# portalusbhub.net
KiCad netlist of a schematic drawn in EasyEDA Pro
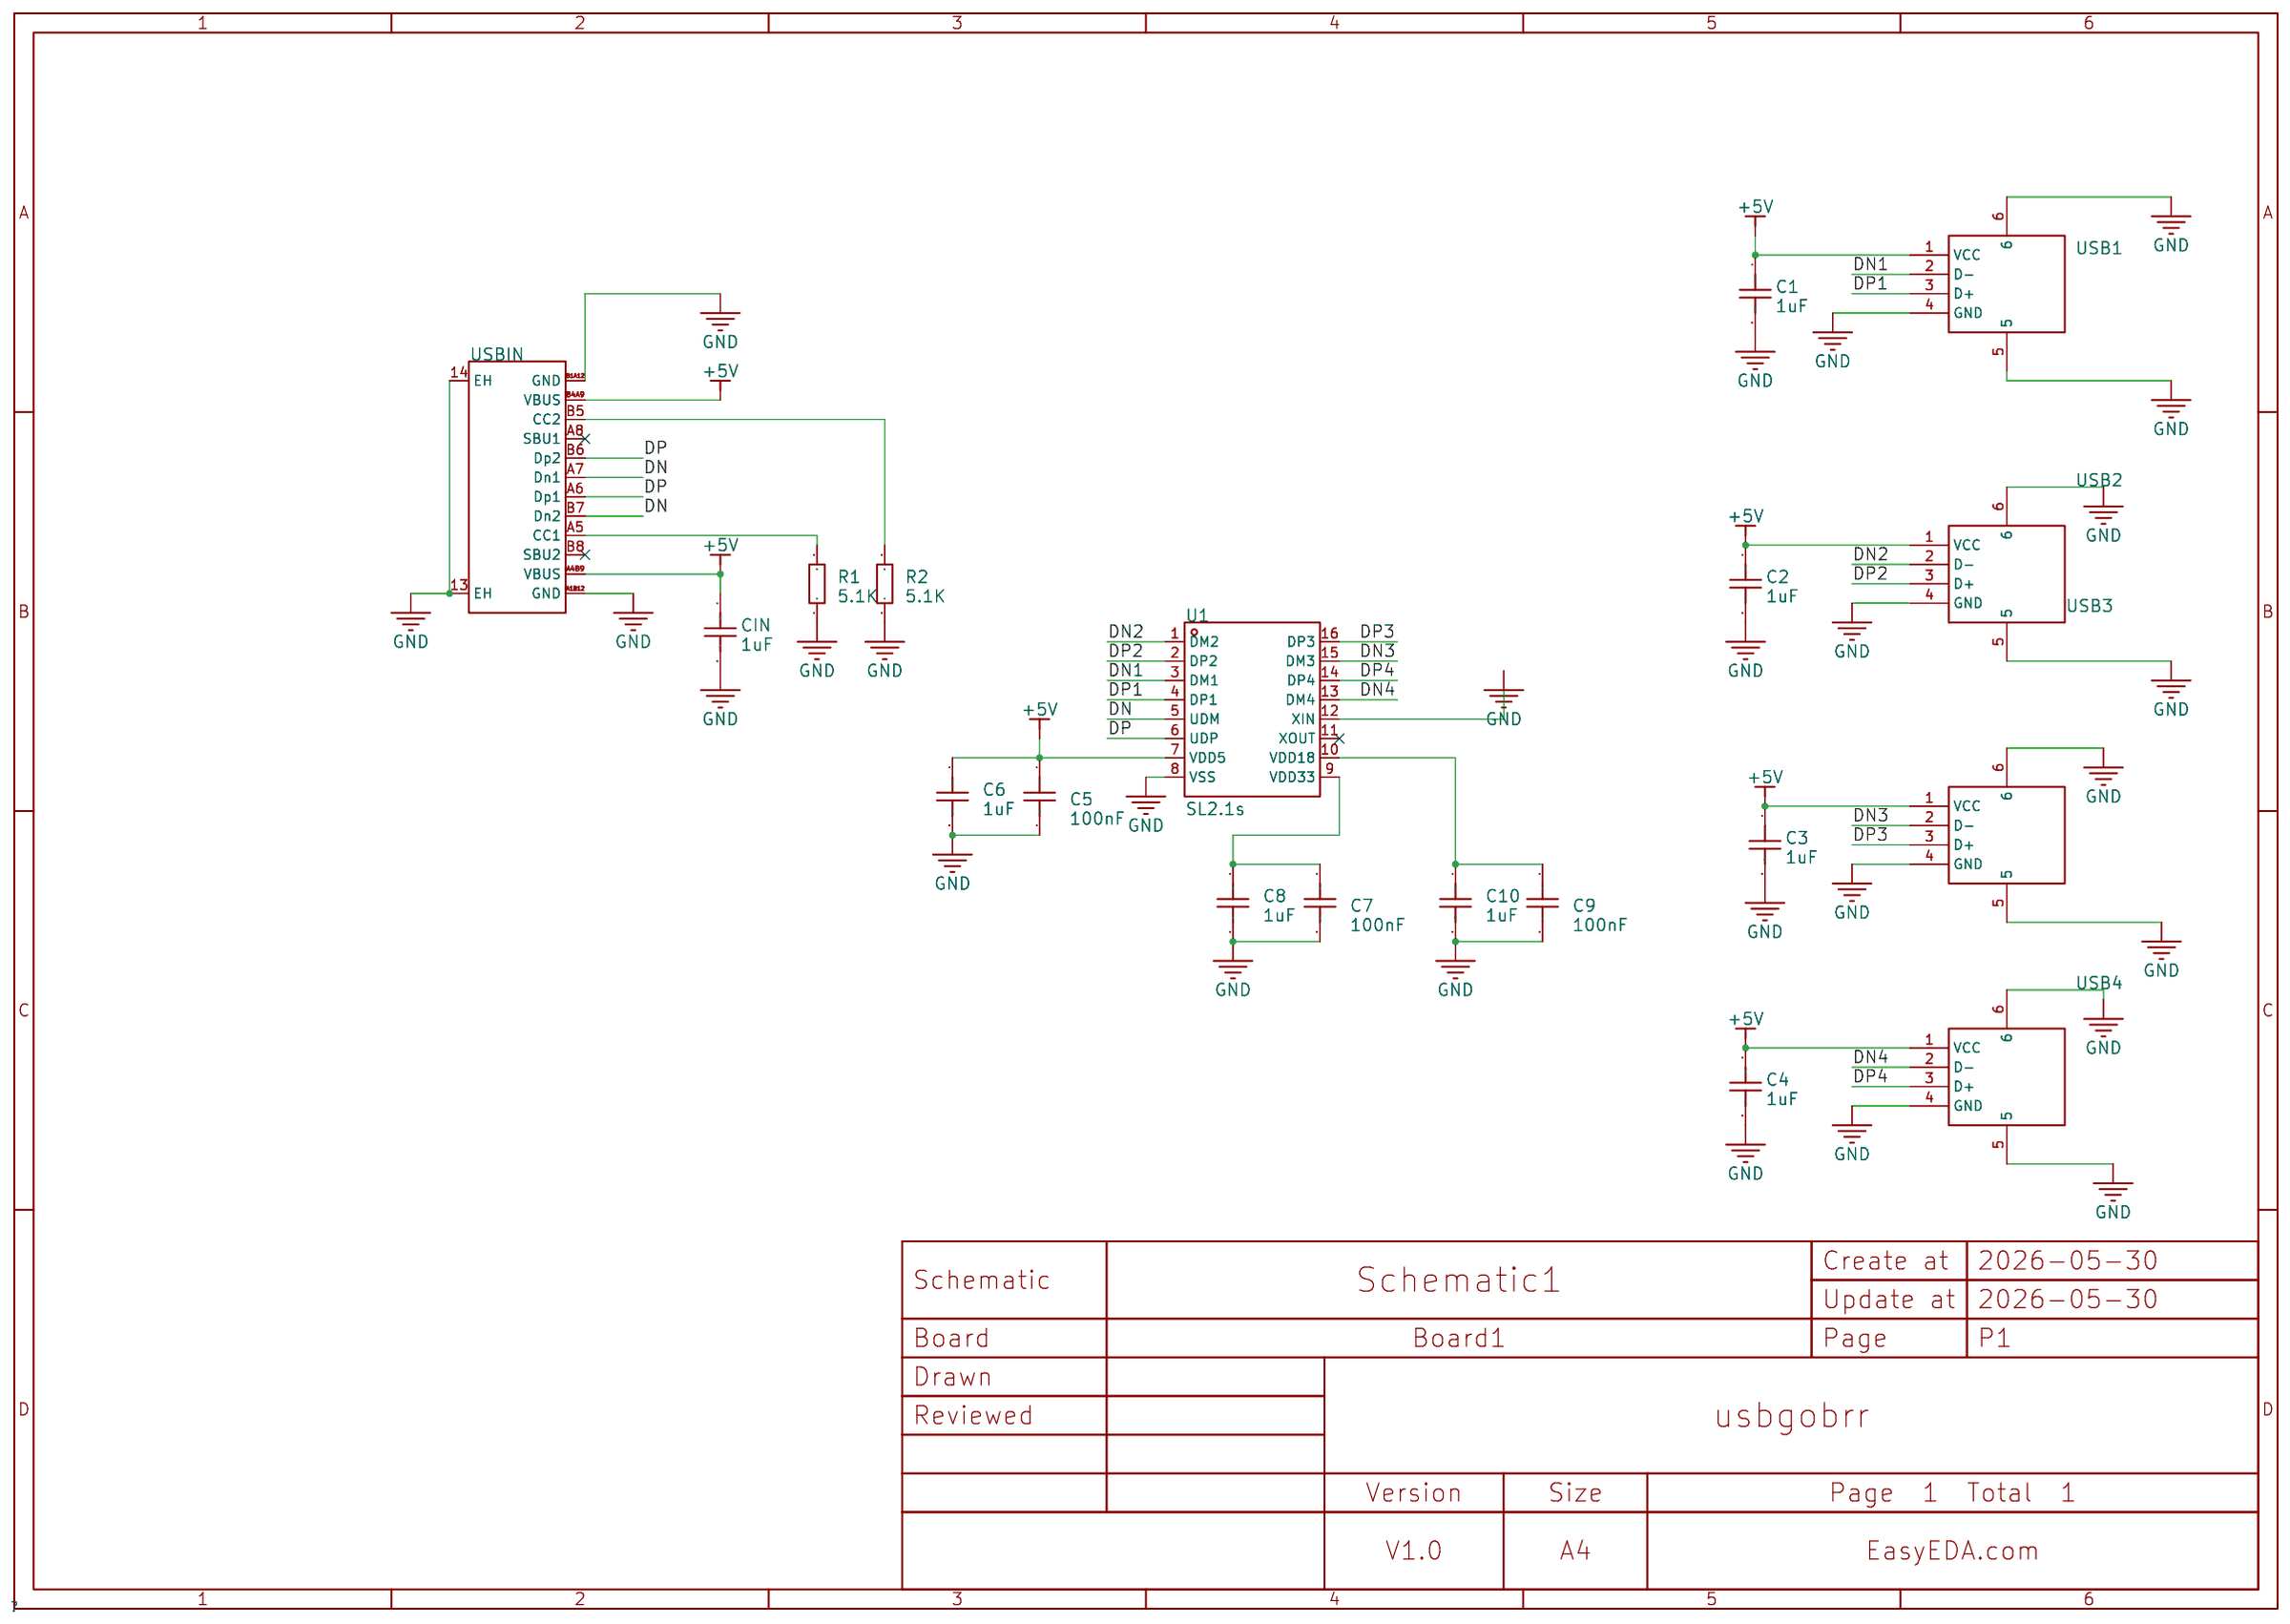
[diagram p0: schematic sheet]

(export (version "E")
  (design (tool "Eeschema 10.0.6"))
  (components
    (comp (ref "C1") (value "1uF") (footprint "easyedapro:C0603") (libsource (lib "easyedapro") (part "CAP")))
    (comp (ref "C2") (value "1uF") (footprint "easyedapro:C0603") (libsource (lib "easyedapro") (part "CAP")))
    (comp (ref "C3") (value "1uF") (footprint "easyedapro:C0603") (libsource (lib "easyedapro") (part "CAP")))
    (comp (ref "C4") (value "1uF") (footprint "easyedapro:C0603") (libsource (lib "easyedapro") (part "CAP")))
    (comp (ref "C5")
      (value "100nF")
      (footprint "easyedapro:C0603")
      (libsource (lib "easyedapro") (part "CAP"))
    )
    (comp (ref "C6") (value "1uF") (footprint "easyedapro:C0603") (libsource (lib "easyedapro") (part "CAP")))
    (comp (ref "C7")
      (value "100nF")
      (footprint "easyedapro:C0603")
      (libsource (lib "easyedapro") (part "CAP"))
    )
    (comp (ref "C8") (value "1uF") (footprint "easyedapro:C0603") (libsource (lib "easyedapro") (part "CAP")))
    (comp (ref "C9")
      (value "100nF")
      (footprint "easyedapro:C0603")
      (libsource (lib "easyedapro") (part "CAP"))
    )
    (comp (ref "C10")
      (value "1uF")
      (footprint "easyedapro:C0603")
      (libsource (lib "easyedapro") (part "CAP"))
    )
    (comp (ref "CIN")
      (value "1uF")
      (footprint "easyedapro:C0603")
      (libsource (lib "easyedapro") (part "CAP"))
    )
    (comp (ref "R1")
      (value "5.1K")
      (footprint "easyedapro:R0603")
      (libsource (lib "easyedapro") (part "Res"))
    )
    (comp (ref "R2")
      (value "5.1K")
      (footprint "easyedapro:R0603")
      (libsource (lib "easyedapro") (part "Res"))
    )
    (comp (ref "U1")
      (value "SL2.1s")
      (footprint "easyedapro:SSOP-16_L4.6-W2.6-P0.53-LS4.0-BL")
      (fields (field (name "Manufacturer") "CoreChips(和芯润德)"))
      (libsource (lib "easyedapro") (part "SL2.1S"))
    )
    (comp (ref "USB1")
      (value "10.0 QHHTZB6.3")
      (footprint "easyedapro:USB-A-TH_10.0QHHTZB6.3")
      (fields (field (name "Manufacturer") "SHOU HAN(首韩)"))
      (libsource (lib "easyedapro") (part "10.0 QHHTZB6.3"))
    )
    (comp (ref "USB2")
      (value "10.0 QHHTZB6.3")
      (footprint "easyedapro:USB-A-TH_10.0QHHTZB6.3")
      (fields (field (name "Manufacturer") "SHOU HAN(首韩)"))
      (libsource (lib "easyedapro") (part "10.0 QHHTZB6.3"))
    )
    (comp (ref "USB3")
      (value "10.0 QHHTZB6.3")
      (footprint "easyedapro:USB-A-TH_10.0QHHTZB6.3")
      (fields (field (name "Manufacturer") "SHOU HAN(首韩)"))
      (libsource (lib "easyedapro") (part "10.0 QHHTZB6.3"))
    )
    (comp (ref "USB4")
      (value "10.0 QHHTZB6.3")
      (footprint "easyedapro:USB-A-TH_10.0QHHTZB6.3")
      (fields (field (name "Manufacturer") "SHOU HAN(首韩)"))
      (libsource (lib "easyedapro") (part "10.0 QHHTZB6.3"))
    )
    (comp (ref "USBIN")
      (value "TYPE-C 16PIN 2MD(073)")
      (footprint "easyedapro:USB-C-SMD_TYPE-C-16PIN-2MD-073")
      (fields (field (name "Manufacturer") "SHOU HAN(首韩)"))
      (libsource (lib "easyedapro") (part "TYPE-C 16PIN 2MD(073)"))
    )
  )
  (nets
    (net (code "1") (name "+5V") (class "Default")
      (node (ref "C1") (pin "1") (pinfunction "1_1") (pintype "input"))
      (node (ref "C2") (pin "1") (pinfunction "1_1") (pintype "input"))
      (node (ref "C3") (pin "1") (pinfunction "1_1") (pintype "input"))
      (node (ref "C4") (pin "1") (pinfunction "1_1") (pintype "input"))
      (node (ref "C5") (pin "1") (pinfunction "1_1") (pintype "input"))
      (node (ref "C6") (pin "1") (pinfunction "1_1") (pintype "input"))
      (node (ref "CIN") (pin "1") (pinfunction "1_1") (pintype "input"))
      (node (ref "U1") (pin "7") (pinfunction "VDD5_7") (pintype "unspecified"))
      (node (ref "USB1") (pin "1") (pinfunction "VCC_1") (pintype "unspecified"))
      (node (ref "USB2") (pin "1") (pinfunction "VCC_1") (pintype "unspecified"))
      (node (ref "USB3") (pin "1") (pinfunction "VCC_1") (pintype "unspecified"))
      (node (ref "USB4") (pin "1") (pinfunction "VCC_1") (pintype "unspecified"))
      (node (ref "USBIN") (pin "A4B9") (pinfunction "VBUS_A4B9") (pintype "unspecified"))
      (node (ref "USBIN") (pin "B4A9") (pinfunction "VBUS_B4A9") (pintype "unspecified"))
    )
    (net (code "2") (name "/DN") (class "Default")
      (node (ref "U1") (pin "5") (pinfunction "UDM_5") (pintype "unspecified"))
      (node (ref "USBIN") (pin "A7") (pinfunction "Dn1_A7") (pintype "unspecified"))
      (node (ref "USBIN") (pin "B7") (pinfunction "Dn2_B7") (pintype "unspecified"))
    )
    (net (code "3") (name "/DN1") (class "Default")
      (node (ref "U1") (pin "3") (pinfunction "DM1_3") (pintype "unspecified"))
      (node (ref "USB1") (pin "2") (pinfunction "D-_2") (pintype "unspecified"))
    )
    (net (code "4") (name "/DN2") (class "Default")
      (node (ref "U1") (pin "1") (pinfunction "DM2_1") (pintype "unspecified"))
      (node (ref "USB2") (pin "2") (pinfunction "D-_2") (pintype "unspecified"))
    )
    (net (code "5") (name "/DN3") (class "Default")
      (node (ref "U1") (pin "15") (pinfunction "DM3_15") (pintype "unspecified"))
      (node (ref "USB3") (pin "2") (pinfunction "D-_2") (pintype "unspecified"))
    )
    (net (code "6") (name "/DN4") (class "Default")
      (node (ref "U1") (pin "13") (pinfunction "DM4_13") (pintype "unspecified"))
      (node (ref "USB4") (pin "2") (pinfunction "D-_2") (pintype "unspecified"))
    )
    (net (code "7") (name "/DP") (class "Default")
      (node (ref "U1") (pin "6") (pinfunction "UDP_6") (pintype "unspecified"))
      (node (ref "USBIN") (pin "A6") (pinfunction "Dp1_A6") (pintype "unspecified"))
      (node (ref "USBIN") (pin "B6") (pinfunction "Dp2_B6") (pintype "unspecified"))
    )
    (net (code "8") (name "/DP1") (class "Default")
      (node (ref "U1") (pin "4") (pinfunction "DP1_4") (pintype "unspecified"))
      (node (ref "USB1") (pin "3") (pinfunction "D+_3") (pintype "unspecified"))
    )
    (net (code "9") (name "/DP2") (class "Default")
      (node (ref "U1") (pin "2") (pinfunction "DP2_2") (pintype "unspecified"))
      (node (ref "USB2") (pin "3") (pinfunction "D+_3") (pintype "unspecified"))
    )
    (net (code "10") (name "/DP3") (class "Default")
      (node (ref "U1") (pin "16") (pinfunction "DP3_16") (pintype "unspecified"))
      (node (ref "USB3") (pin "3") (pinfunction "D+_3") (pintype "unspecified"))
    )
    (net (code "11") (name "/DP4") (class "Default")
      (node (ref "U1") (pin "14") (pinfunction "DP4_14") (pintype "unspecified"))
      (node (ref "USB4") (pin "3") (pinfunction "D+_3") (pintype "unspecified"))
    )
    (net (code "12") (name "GND") (class "Default")
      (node (ref "C1") (pin "2") (pinfunction "2_2") (pintype "input"))
      (node (ref "C10") (pin "2") (pinfunction "2_2") (pintype "input"))
      (node (ref "C2") (pin "2") (pinfunction "2_2") (pintype "input"))
      (node (ref "C3") (pin "2") (pinfunction "2_2") (pintype "input"))
      (node (ref "C4") (pin "2") (pinfunction "2_2") (pintype "input"))
      (node (ref "C5") (pin "2") (pinfunction "2_2") (pintype "input"))
      (node (ref "C6") (pin "2") (pinfunction "2_2") (pintype "input"))
      (node (ref "C7") (pin "2") (pinfunction "2_2") (pintype "input"))
      (node (ref "C8") (pin "2") (pinfunction "2_2") (pintype "input"))
      (node (ref "C9") (pin "2") (pinfunction "2_2") (pintype "input"))
      (node (ref "CIN") (pin "2") (pinfunction "2_2") (pintype "input"))
      (node (ref "R1") (pin "1") (pinfunction "1_1") (pintype "input"))
      (node (ref "R2") (pin "1") (pinfunction "1_1") (pintype "input"))
      (node (ref "U1") (pin "12") (pinfunction "XIN_12") (pintype "unspecified"))
      (node (ref "U1") (pin "8") (pinfunction "VSS_8") (pintype "unspecified"))
      (node (ref "USB1") (pin "4") (pinfunction "GND_4") (pintype "unspecified"))
      (node (ref "USB1") (pin "5") (pinfunction "5_5") (pintype "unspecified"))
      (node (ref "USB1") (pin "6") (pinfunction "6_6") (pintype "unspecified"))
      (node (ref "USB2") (pin "4") (pinfunction "GND_4") (pintype "unspecified"))
      (node (ref "USB2") (pin "5") (pinfunction "5_5") (pintype "unspecified"))
      (node (ref "USB2") (pin "6") (pinfunction "6_6") (pintype "unspecified"))
      (node (ref "USB3") (pin "4") (pinfunction "GND_4") (pintype "unspecified"))
      (node (ref "USB3") (pin "5") (pinfunction "5_5") (pintype "unspecified"))
      (node (ref "USB3") (pin "6") (pinfunction "6_6") (pintype "unspecified"))
      (node (ref "USB4") (pin "4") (pinfunction "GND_4") (pintype "unspecified"))
      (node (ref "USB4") (pin "5") (pinfunction "5_5") (pintype "unspecified"))
      (node (ref "USB4") (pin "6") (pinfunction "6_6") (pintype "unspecified"))
      (node (ref "USBIN") (pin "13") (pinfunction "EH_13") (pintype "unspecified"))
      (node (ref "USBIN") (pin "14") (pinfunction "EH_14") (pintype "unspecified"))
      (node (ref "USBIN") (pin "A1B12") (pinfunction "GND_A1B12") (pintype "unspecified"))
      (node (ref "USBIN") (pin "B1A12") (pinfunction "GND_B1A12") (pintype "unspecified"))
    )
    (net (code "13") (name "Net-(U1-VDD18)") (class "Default")
      (node (ref "C10") (pin "1") (pinfunction "1_1") (pintype "input"))
      (node (ref "C9") (pin "1") (pinfunction "1_1") (pintype "input"))
      (node (ref "U1") (pin "10") (pinfunction "VDD18_10") (pintype "unspecified"))
    )
    (net (code "14") (name "Net-(U1-VDD33)") (class "Default")
      (node (ref "C7") (pin "1") (pinfunction "1_1") (pintype "input"))
      (node (ref "C8") (pin "1") (pinfunction "1_1") (pintype "input"))
      (node (ref "U1") (pin "9") (pinfunction "VDD33_9") (pintype "unspecified"))
    )
    (net (code "15") (name "Net-(USBIN-CC1)") (class "Default")
      (node (ref "R1") (pin "2") (pinfunction "2_2") (pintype "input"))
      (node (ref "USBIN") (pin "A5") (pinfunction "CC1_A5") (pintype "unspecified"))
    )
    (net (code "16") (name "Net-(USBIN-CC2)") (class "Default")
      (node (ref "R2") (pin "2") (pinfunction "2_2") (pintype "input"))
      (node (ref "USBIN") (pin "B5") (pinfunction "CC2_B5") (pintype "unspecified"))
    )
    (net (code "17") (name "unconnected-(U1-XOUT-Pad11)") (class "Default")
      (node (ref "U1") (pin "11") (pinfunction "XOUT_11") (pintype "unspecified+no_connect"))
    )
    (net (code "18") (name "unconnected-(USBIN-SBU1-PadA8)") (class "Default")
      (node (ref "USBIN") (pin "A8") (pinfunction "SBU1_A8") (pintype "unspecified+no_connect"))
    )
    (net (code "19") (name "unconnected-(USBIN-SBU2-PadB8)") (class "Default")
      (node (ref "USBIN") (pin "B8") (pinfunction "SBU2_B8") (pintype "unspecified+no_connect"))
    )
  )
)
